# MainADC.net
KiCad netlist of a schematic drawn in Altium Designer
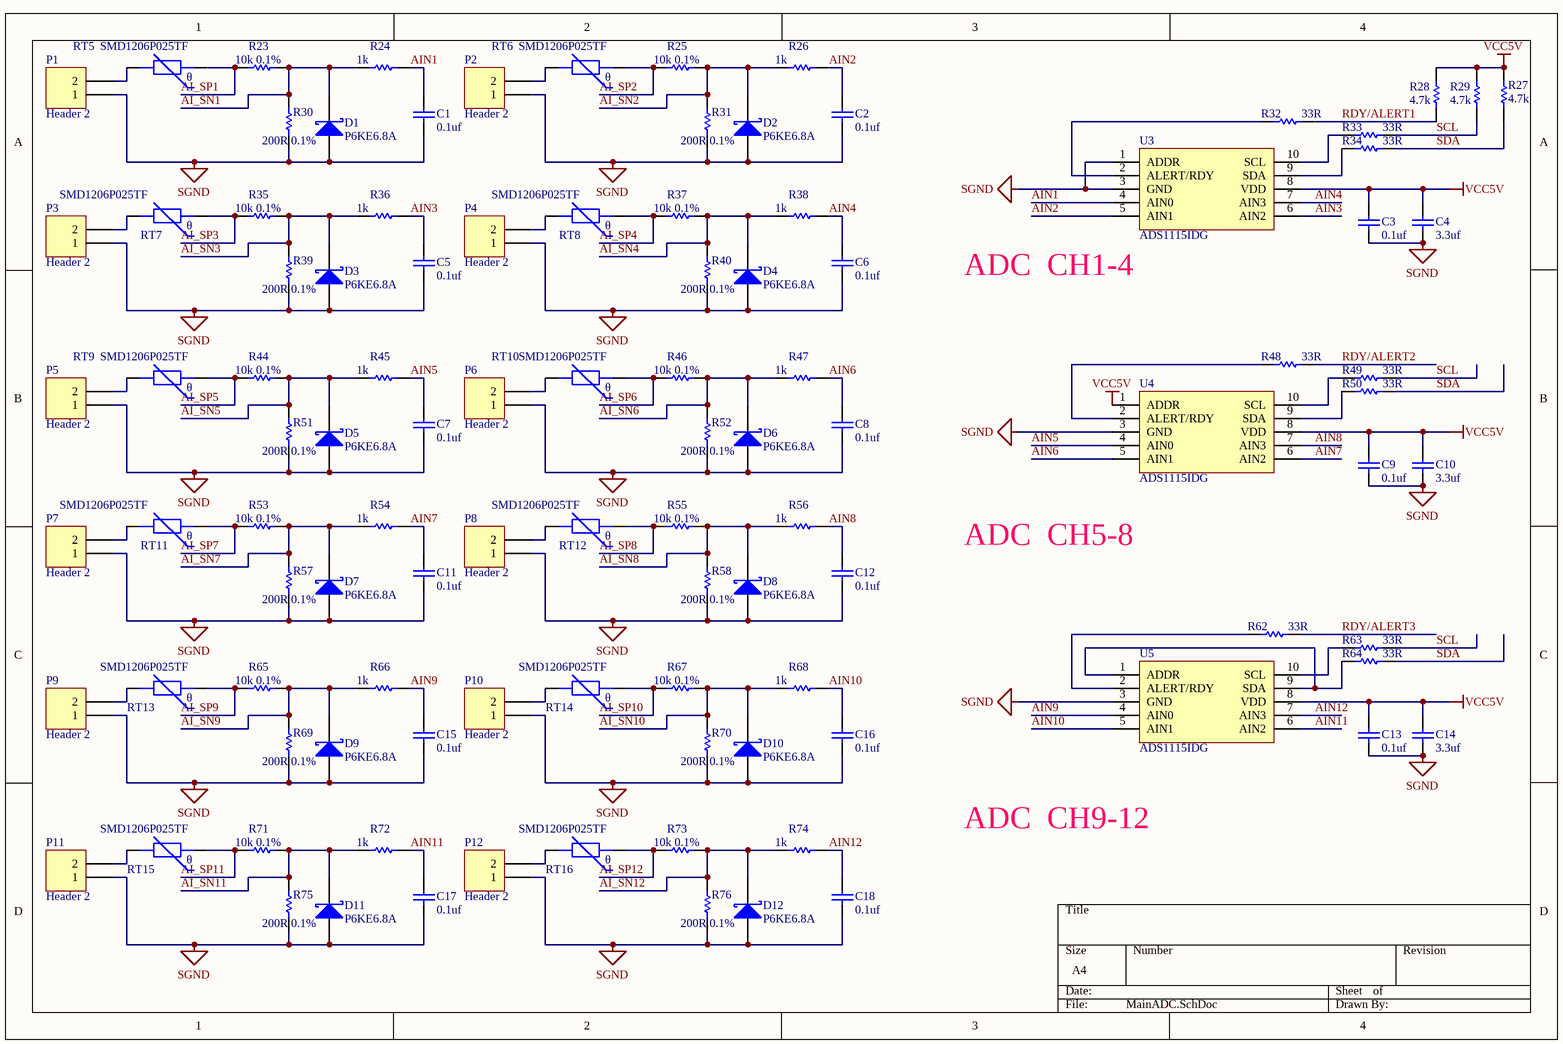
[diagram p0: MainADC.SchDoc]

(export (version "E")
  (design (tool "Eeschema 10.0.6"))
  (components
    (comp (ref "C1")
      (value "0.1uf")
      (footprint "C0805")
      (description "Capacitor")
      (fields
        (field (name "MANUFACTURER") "Generic Components")
        (field (name "Comment") "Cap")
        (field (name "PUBLISHER") "Altium Hobart Technology Centre")
      )
      (libsource (lib "Miscellaneous Devices") (part "Cap"))
    )
    (comp (ref "C2")
      (value "0.1uf")
      (footprint "C0805")
      (description "Capacitor")
      (fields
        (field (name "MANUFACTURER") "Generic Components")
        (field (name "Comment") "Cap")
        (field (name "PUBLISHER") "Altium Hobart Technology Centre")
      )
      (libsource (lib "Miscellaneous Devices") (part "Cap"))
    )
    (comp (ref "C3")
      (value "0.1uf")
      (footprint "C0805")
      (description "Capacitor")
      (fields
        (field (name "MANUFACTURER") "Generic Components")
        (field (name "Comment") "Cap")
        (field (name "PUBLISHER") "Altium Hobart Technology Centre")
      )
      (libsource (lib "Miscellaneous Devices") (part "Cap"))
    )
    (comp (ref "C4")
      (value "3.3uf")
      (footprint "C0805")
      (description "Capacitor")
      (fields
        (field (name "MANUFACTURER") "Generic Components")
        (field (name "Comment") "Cap")
        (field (name "PUBLISHER") "Altium Hobart Technology Centre")
      )
      (libsource (lib "Miscellaneous Devices") (part "Cap"))
    )
    (comp (ref "C5")
      (value "0.1uf")
      (footprint "C0805")
      (description "Capacitor")
      (fields
        (field (name "MANUFACTURER") "Generic Components")
        (field (name "Comment") "Cap")
        (field (name "PUBLISHER") "Altium Hobart Technology Centre")
      )
      (libsource (lib "Miscellaneous Devices") (part "Cap"))
    )
    (comp (ref "C6")
      (value "0.1uf")
      (footprint "C0805")
      (description "Capacitor")
      (fields
        (field (name "MANUFACTURER") "Generic Components")
        (field (name "Comment") "Cap")
        (field (name "PUBLISHER") "Altium Hobart Technology Centre")
      )
      (libsource (lib "Miscellaneous Devices") (part "Cap"))
    )
    (comp (ref "C7")
      (value "0.1uf")
      (footprint "C0805")
      (description "Capacitor")
      (fields
        (field (name "MANUFACTURER") "Generic Components")
        (field (name "Comment") "Cap")
        (field (name "PUBLISHER") "Altium Hobart Technology Centre")
      )
      (libsource (lib "Miscellaneous Devices") (part "Cap"))
    )
    (comp (ref "C8")
      (value "0.1uf")
      (footprint "C0805")
      (description "Capacitor")
      (fields
        (field (name "MANUFACTURER") "Generic Components")
        (field (name "Comment") "Cap")
        (field (name "PUBLISHER") "Altium Hobart Technology Centre")
      )
      (libsource (lib "Miscellaneous Devices") (part "Cap"))
    )
    (comp (ref "C9")
      (value "0.1uf")
      (footprint "C0805")
      (description "Capacitor")
      (fields
        (field (name "MANUFACTURER") "Generic Components")
        (field (name "Comment") "Cap")
        (field (name "PUBLISHER") "Altium Hobart Technology Centre")
      )
      (libsource (lib "Miscellaneous Devices") (part "Cap"))
    )
    (comp (ref "C10")
      (value "3.3uf")
      (footprint "C0805")
      (description "Capacitor")
      (fields
        (field (name "MANUFACTURER") "Generic Components")
        (field (name "Comment") "Cap")
        (field (name "PUBLISHER") "Altium Hobart Technology Centre")
      )
      (libsource (lib "Miscellaneous Devices") (part "Cap"))
    )
    (comp (ref "C11")
      (value "0.1uf")
      (footprint "C0805")
      (description "Capacitor")
      (fields
        (field (name "MANUFACTURER") "Generic Components")
        (field (name "Comment") "Cap")
        (field (name "PUBLISHER") "Altium Hobart Technology Centre")
      )
      (libsource (lib "Miscellaneous Devices") (part "Cap"))
    )
    (comp (ref "C12")
      (value "0.1uf")
      (footprint "C0805")
      (description "Capacitor")
      (fields
        (field (name "MANUFACTURER") "Generic Components")
        (field (name "Comment") "Cap")
        (field (name "PUBLISHER") "Altium Hobart Technology Centre")
      )
      (libsource (lib "Miscellaneous Devices") (part "Cap"))
    )
    (comp (ref "C13")
      (value "0.1uf")
      (footprint "C0805")
      (description "Capacitor")
      (fields
        (field (name "MANUFACTURER") "Generic Components")
        (field (name "Comment") "Cap")
        (field (name "PUBLISHER") "Altium Hobart Technology Centre")
      )
      (libsource (lib "Miscellaneous Devices") (part "Cap"))
    )
    (comp (ref "C14")
      (value "3.3uf")
      (footprint "C0805")
      (description "Capacitor")
      (fields
        (field (name "MANUFACTURER") "Generic Components")
        (field (name "Comment") "Cap")
        (field (name "PUBLISHER") "Altium Hobart Technology Centre")
      )
      (libsource (lib "Miscellaneous Devices") (part "Cap"))
    )
    (comp (ref "C15")
      (value "0.1uf")
      (footprint "C0805")
      (description "Capacitor")
      (fields
        (field (name "MANUFACTURER") "Generic Components")
        (field (name "Comment") "Cap")
        (field (name "PUBLISHER") "Altium Hobart Technology Centre")
      )
      (libsource (lib "Miscellaneous Devices") (part "Cap"))
    )
    (comp (ref "C16")
      (value "0.1uf")
      (footprint "C0805")
      (description "Capacitor")
      (fields
        (field (name "MANUFACTURER") "Generic Components")
        (field (name "Comment") "Cap")
        (field (name "PUBLISHER") "Altium Hobart Technology Centre")
      )
      (libsource (lib "Miscellaneous Devices") (part "Cap"))
    )
    (comp (ref "C17")
      (value "0.1uf")
      (footprint "C0805")
      (description "Capacitor")
      (fields
        (field (name "MANUFACTURER") "Generic Components")
        (field (name "Comment") "Cap")
        (field (name "PUBLISHER") "Altium Hobart Technology Centre")
      )
      (libsource (lib "Miscellaneous Devices") (part "Cap"))
    )
    (comp (ref "C18")
      (value "0.1uf")
      (footprint "C0805")
      (description "Capacitor")
      (fields
        (field (name "MANUFACTURER") "Generic Components")
        (field (name "Comment") "Cap")
        (field (name "PUBLISHER") "Altium Hobart Technology Centre")
      )
      (libsource (lib "Miscellaneous Devices") (part "Cap"))
    )
    (comp (ref "D1")
      (value "P6KE6.8A")
      (footprint "SMB")
      (description "Schottky Diode")
      (fields (field (name "PUBLISHER") "Altium Limited"))
      (libsource (lib "Miscellaneous Devices") (part "D Schottky"))
    )
    (comp (ref "D2")
      (value "P6KE6.8A")
      (footprint "SMB")
      (description "Schottky Diode")
      (fields (field (name "PUBLISHER") "Altium Limited"))
      (libsource (lib "Miscellaneous Devices") (part "D Schottky"))
    )
    (comp (ref "D3")
      (value "P6KE6.8A")
      (footprint "SMB")
      (description "Schottky Diode")
      (fields (field (name "PUBLISHER") "Altium Limited"))
      (libsource (lib "Miscellaneous Devices") (part "D Schottky"))
    )
    (comp (ref "D4")
      (value "P6KE6.8A")
      (footprint "SMB")
      (description "Schottky Diode")
      (fields (field (name "PUBLISHER") "Altium Limited"))
      (libsource (lib "Miscellaneous Devices") (part "D Schottky"))
    )
    (comp (ref "D5")
      (value "P6KE6.8A")
      (footprint "SMB")
      (description "Schottky Diode")
      (fields (field (name "PUBLISHER") "Altium Limited"))
      (libsource (lib "Miscellaneous Devices") (part "D Schottky"))
    )
    (comp (ref "D6")
      (value "P6KE6.8A")
      (footprint "SMB")
      (description "Schottky Diode")
      (fields (field (name "PUBLISHER") "Altium Limited"))
      (libsource (lib "Miscellaneous Devices") (part "D Schottky"))
    )
    (comp (ref "D7")
      (value "P6KE6.8A")
      (footprint "SMB")
      (description "Schottky Diode")
      (fields (field (name "PUBLISHER") "Altium Limited"))
      (libsource (lib "Miscellaneous Devices") (part "D Schottky"))
    )
    (comp (ref "D8")
      (value "P6KE6.8A")
      (footprint "SMB")
      (description "Schottky Diode")
      (fields (field (name "PUBLISHER") "Altium Limited"))
      (libsource (lib "Miscellaneous Devices") (part "D Schottky"))
    )
    (comp (ref "D9")
      (value "P6KE6.8A")
      (footprint "SMB")
      (description "Schottky Diode")
      (fields (field (name "PUBLISHER") "Altium Limited"))
      (libsource (lib "Miscellaneous Devices") (part "D Schottky"))
    )
    (comp (ref "D10")
      (value "P6KE6.8A")
      (footprint "SMB")
      (description "Schottky Diode")
      (fields (field (name "PUBLISHER") "Altium Limited"))
      (libsource (lib "Miscellaneous Devices") (part "D Schottky"))
    )
    (comp (ref "D11")
      (value "P6KE6.8A")
      (footprint "SMB")
      (description "Schottky Diode")
      (fields (field (name "PUBLISHER") "Altium Limited"))
      (libsource (lib "Miscellaneous Devices") (part "D Schottky"))
    )
    (comp (ref "D12")
      (value "P6KE6.8A")
      (footprint "SMB")
      (description "Schottky Diode")
      (fields (field (name "PUBLISHER") "Altium Limited"))
      (libsource (lib "Miscellaneous Devices") (part "D Schottky"))
    )
    (comp (ref "P1")
      (value "Header 2")
      (footprint "JIEKE_2PX508")
      (description "Header, 2-Pin")
      (fields (field (name "PUBLISHER") "Altium Limited"))
      (libsource (lib "Miscellaneous Connectors") (part "Header 2"))
    )
    (comp (ref "P2")
      (value "Header 2")
      (footprint "JIEKE_2PX508")
      (description "Header, 2-Pin")
      (fields (field (name "PUBLISHER") "Altium Limited"))
      (libsource (lib "Miscellaneous Connectors") (part "Header 2"))
    )
    (comp (ref "P3")
      (value "Header 2")
      (footprint "JIEKE_2PX508")
      (description "Header, 2-Pin")
      (fields (field (name "PUBLISHER") "Altium Limited"))
      (libsource (lib "Miscellaneous Connectors") (part "Header 2"))
    )
    (comp (ref "P4")
      (value "Header 2")
      (footprint "JIEKE_2PX508")
      (description "Header, 2-Pin")
      (fields (field (name "PUBLISHER") "Altium Limited"))
      (libsource (lib "Miscellaneous Connectors") (part "Header 2"))
    )
    (comp (ref "P5")
      (value "Header 2")
      (footprint "JIEKE_2PX508")
      (description "Header, 2-Pin")
      (fields (field (name "PUBLISHER") "Altium Limited"))
      (libsource (lib "Miscellaneous Connectors") (part "Header 2"))
    )
    (comp (ref "P6")
      (value "Header 2")
      (footprint "JIEKE_2PX508")
      (description "Header, 2-Pin")
      (fields (field (name "PUBLISHER") "Altium Limited"))
      (libsource (lib "Miscellaneous Connectors") (part "Header 2"))
    )
    (comp (ref "P7")
      (value "Header 2")
      (footprint "JIEKE_2PX508")
      (description "Header, 2-Pin")
      (fields (field (name "PUBLISHER") "Altium Limited"))
      (libsource (lib "Miscellaneous Connectors") (part "Header 2"))
    )
    (comp (ref "P8")
      (value "Header 2")
      (footprint "JIEKE_2PX508")
      (description "Header, 2-Pin")
      (fields (field (name "PUBLISHER") "Altium Limited"))
      (libsource (lib "Miscellaneous Connectors") (part "Header 2"))
    )
    (comp (ref "P9")
      (value "Header 2")
      (footprint "JIEKE_2PX508")
      (description "Header, 2-Pin")
      (fields (field (name "PUBLISHER") "Altium Limited"))
      (libsource (lib "Miscellaneous Connectors") (part "Header 2"))
    )
    (comp (ref "P10")
      (value "Header 2")
      (footprint "JIEKE_2PX508")
      (description "Header, 2-Pin")
      (fields (field (name "PUBLISHER") "Altium Limited"))
      (libsource (lib "Miscellaneous Connectors") (part "Header 2"))
    )
    (comp (ref "P11")
      (value "Header 2")
      (footprint "JIEKE_2PX508")
      (description "Header, 2-Pin")
      (fields (field (name "PUBLISHER") "Altium Limited"))
      (libsource (lib "Miscellaneous Connectors") (part "Header 2"))
    )
    (comp (ref "P12")
      (value "Header 2")
      (footprint "JIEKE_2PX508")
      (description "Header, 2-Pin")
      (fields (field (name "PUBLISHER") "Altium Limited"))
      (libsource (lib "Miscellaneous Connectors") (part "Header 2"))
    )
    (comp (ref "R23")
      (value "10k 0.1%")
      (footprint "0805")
      (description "Semiconductor Resistor")
      (fields (field (name "Comment") "Res Semi") (field (name "PUBLISHER") "Altium Limited"))
      (libsource (lib "Miscellaneous Devices") (part "Res Semi"))
    )
    (comp (ref "R24")
      (value "1k")
      (footprint "0805")
      (description "Semiconductor Resistor")
      (fields (field (name "Comment") "Res Semi") (field (name "PUBLISHER") "Altium Limited"))
      (libsource (lib "Miscellaneous Devices") (part "Res Semi"))
    )
    (comp (ref "R25")
      (value "10k 0.1%")
      (footprint "0805")
      (description "Semiconductor Resistor")
      (fields (field (name "Comment") "Res Semi") (field (name "PUBLISHER") "Altium Limited"))
      (libsource (lib "Miscellaneous Devices") (part "Res Semi"))
    )
    (comp (ref "R26")
      (value "1k")
      (footprint "0805")
      (description "Semiconductor Resistor")
      (fields (field (name "Comment") "Res Semi") (field (name "PUBLISHER") "Altium Limited"))
      (libsource (lib "Miscellaneous Devices") (part "Res Semi"))
    )
    (comp (ref "R27")
      (value "4.7k")
      (footprint "0805")
      (description "Semiconductor Resistor")
      (fields (field (name "Comment") "Res Semi") (field (name "PUBLISHER") "Altium Limited"))
      (libsource (lib "Miscellaneous Devices") (part "Res Semi"))
    )
    (comp (ref "R28")
      (value "4.7k")
      (footprint "0805")
      (description "Semiconductor Resistor")
      (fields (field (name "Comment") "Res Semi") (field (name "PUBLISHER") "Altium Limited"))
      (libsource (lib "Miscellaneous Devices") (part "Res Semi"))
    )
    (comp (ref "R29")
      (value "4.7k")
      (footprint "0805")
      (description "Semiconductor Resistor")
      (fields (field (name "Comment") "Res Semi") (field (name "PUBLISHER") "Altium Limited"))
      (libsource (lib "Miscellaneous Devices") (part "Res Semi"))
    )
    (comp (ref "R30")
      (value "200R 0.1%")
      (footprint "0805")
      (description "Semiconductor Resistor")
      (fields (field (name "Comment") "Res Semi") (field (name "PUBLISHER") "Altium Limited"))
      (libsource (lib "Miscellaneous Devices") (part "Res Semi"))
    )
    (comp (ref "R31")
      (value "200R 0.1%")
      (footprint "0805")
      (description "Semiconductor Resistor")
      (fields (field (name "Comment") "Res Semi") (field (name "PUBLISHER") "Altium Limited"))
      (libsource (lib "Miscellaneous Devices") (part "Res Semi"))
    )
    (comp (ref "R32")
      (value "33R")
      (footprint "0805")
      (description "Semiconductor Resistor")
      (fields (field (name "Comment") "Res Semi") (field (name "PUBLISHER") "Altium Limited"))
      (libsource (lib "Miscellaneous Devices") (part "Res Semi"))
    )
    (comp (ref "R33")
      (value "33R")
      (footprint "0805")
      (description "Semiconductor Resistor")
      (fields (field (name "Comment") "Res Semi") (field (name "PUBLISHER") "Altium Limited"))
      (libsource (lib "Miscellaneous Devices") (part "Res Semi"))
    )
    (comp (ref "R34")
      (value "33R")
      (footprint "0805")
      (description "Semiconductor Resistor")
      (fields (field (name "Comment") "Res Semi") (field (name "PUBLISHER") "Altium Limited"))
      (libsource (lib "Miscellaneous Devices") (part "Res Semi"))
    )
    (comp (ref "R35")
      (value "10k 0.1%")
      (footprint "0805")
      (description "Semiconductor Resistor")
      (fields (field (name "Comment") "Res Semi") (field (name "PUBLISHER") "Altium Limited"))
      (libsource (lib "Miscellaneous Devices") (part "Res Semi"))
    )
    (comp (ref "R36")
      (value "1k")
      (footprint "0805")
      (description "Semiconductor Resistor")
      (fields (field (name "Comment") "Res Semi") (field (name "PUBLISHER") "Altium Limited"))
      (libsource (lib "Miscellaneous Devices") (part "Res Semi"))
    )
    (comp (ref "R37")
      (value "10k 0.1%")
      (footprint "0805")
      (description "Semiconductor Resistor")
      (fields (field (name "Comment") "Res Semi") (field (name "PUBLISHER") "Altium Limited"))
      (libsource (lib "Miscellaneous Devices") (part "Res Semi"))
    )
    (comp (ref "R38")
      (value "1k")
      (footprint "0805")
      (description "Semiconductor Resistor")
      (fields (field (name "Comment") "Res Semi") (field (name "PUBLISHER") "Altium Limited"))
      (libsource (lib "Miscellaneous Devices") (part "Res Semi"))
    )
    (comp (ref "R39")
      (value "200R 0.1%")
      (footprint "0805")
      (description "Semiconductor Resistor")
      (fields (field (name "Comment") "Res Semi") (field (name "PUBLISHER") "Altium Limited"))
      (libsource (lib "Miscellaneous Devices") (part "Res Semi"))
    )
    (comp (ref "R40")
      (value "200R 0.1%")
      (footprint "0805")
      (description "Semiconductor Resistor")
      (fields (field (name "Comment") "Res Semi") (field (name "PUBLISHER") "Altium Limited"))
      (libsource (lib "Miscellaneous Devices") (part "Res Semi"))
    )
    (comp (ref "R44")
      (value "10k 0.1%")
      (footprint "0805")
      (description "Semiconductor Resistor")
      (fields (field (name "Comment") "Res Semi") (field (name "PUBLISHER") "Altium Limited"))
      (libsource (lib "Miscellaneous Devices") (part "Res Semi"))
    )
    (comp (ref "R45")
      (value "1k")
      (footprint "0805")
      (description "Semiconductor Resistor")
      (fields (field (name "Comment") "Res Semi") (field (name "PUBLISHER") "Altium Limited"))
      (libsource (lib "Miscellaneous Devices") (part "Res Semi"))
    )
    (comp (ref "R46")
      (value "10k 0.1%")
      (footprint "0805")
      (description "Semiconductor Resistor")
      (fields (field (name "Comment") "Res Semi") (field (name "PUBLISHER") "Altium Limited"))
      (libsource (lib "Miscellaneous Devices") (part "Res Semi"))
    )
    (comp (ref "R47")
      (value "1k")
      (footprint "0805")
      (description "Semiconductor Resistor")
      (fields (field (name "Comment") "Res Semi") (field (name "PUBLISHER") "Altium Limited"))
      (libsource (lib "Miscellaneous Devices") (part "Res Semi"))
    )
    (comp (ref "R48")
      (value "33R")
      (footprint "0805")
      (description "Semiconductor Resistor")
      (fields (field (name "Comment") "Res Semi") (field (name "PUBLISHER") "Altium Limited"))
      (libsource (lib "Miscellaneous Devices") (part "Res Semi"))
    )
    (comp (ref "R49")
      (value "33R")
      (footprint "0805")
      (description "Semiconductor Resistor")
      (fields (field (name "Comment") "Res Semi") (field (name "PUBLISHER") "Altium Limited"))
      (libsource (lib "Miscellaneous Devices") (part "Res Semi"))
    )
    (comp (ref "R50")
      (value "33R")
      (footprint "0805")
      (description "Semiconductor Resistor")
      (fields (field (name "Comment") "Res Semi") (field (name "PUBLISHER") "Altium Limited"))
      (libsource (lib "Miscellaneous Devices") (part "Res Semi"))
    )
    (comp (ref "R51")
      (value "200R 0.1%")
      (footprint "0805")
      (description "Semiconductor Resistor")
      (fields (field (name "Comment") "Res Semi") (field (name "PUBLISHER") "Altium Limited"))
      (libsource (lib "Miscellaneous Devices") (part "Res Semi"))
    )
    (comp (ref "R52")
      (value "200R 0.1%")
      (footprint "0805")
      (description "Semiconductor Resistor")
      (fields (field (name "Comment") "Res Semi") (field (name "PUBLISHER") "Altium Limited"))
      (libsource (lib "Miscellaneous Devices") (part "Res Semi"))
    )
    (comp (ref "R53")
      (value "10k 0.1%")
      (footprint "0805")
      (description "Semiconductor Resistor")
      (fields (field (name "Comment") "Res Semi") (field (name "PUBLISHER") "Altium Limited"))
      (libsource (lib "Miscellaneous Devices") (part "Res Semi"))
    )
    (comp (ref "R54")
      (value "1k")
      (footprint "0805")
      (description "Semiconductor Resistor")
      (fields (field (name "Comment") "Res Semi") (field (name "PUBLISHER") "Altium Limited"))
      (libsource (lib "Miscellaneous Devices") (part "Res Semi"))
    )
    (comp (ref "R55")
      (value "10k 0.1%")
      (footprint "0805")
      (description "Semiconductor Resistor")
      (fields (field (name "Comment") "Res Semi") (field (name "PUBLISHER") "Altium Limited"))
      (libsource (lib "Miscellaneous Devices") (part "Res Semi"))
    )
    (comp (ref "R56")
      (value "1k")
      (footprint "0805")
      (description "Semiconductor Resistor")
      (fields (field (name "Comment") "Res Semi") (field (name "PUBLISHER") "Altium Limited"))
      (libsource (lib "Miscellaneous Devices") (part "Res Semi"))
    )
    (comp (ref "R57")
      (value "200R 0.1%")
      (footprint "0805")
      (description "Semiconductor Resistor")
      (fields (field (name "Comment") "Res Semi") (field (name "PUBLISHER") "Altium Limited"))
      (libsource (lib "Miscellaneous Devices") (part "Res Semi"))
    )
    (comp (ref "R58")
      (value "200R 0.1%")
      (footprint "0805")
      (description "Semiconductor Resistor")
      (fields (field (name "Comment") "Res Semi") (field (name "PUBLISHER") "Altium Limited"))
      (libsource (lib "Miscellaneous Devices") (part "Res Semi"))
    )
    (comp (ref "R62")
      (value "33R")
      (footprint "0805")
      (description "Semiconductor Resistor")
      (fields (field (name "Comment") "Res Semi") (field (name "PUBLISHER") "Altium Limited"))
      (libsource (lib "Miscellaneous Devices") (part "Res Semi"))
    )
    (comp (ref "R63")
      (value "33R")
      (footprint "0805")
      (description "Semiconductor Resistor")
      (fields (field (name "Comment") "Res Semi") (field (name "PUBLISHER") "Altium Limited"))
      (libsource (lib "Miscellaneous Devices") (part "Res Semi"))
    )
    (comp (ref "R64")
      (value "33R")
      (footprint "0805")
      (description "Semiconductor Resistor")
      (fields (field (name "Comment") "Res Semi") (field (name "PUBLISHER") "Altium Limited"))
      (libsource (lib "Miscellaneous Devices") (part "Res Semi"))
    )
    (comp (ref "R65")
      (value "10k 0.1%")
      (footprint "0805")
      (description "Semiconductor Resistor")
      (fields (field (name "Comment") "Res Semi") (field (name "PUBLISHER") "Altium Limited"))
      (libsource (lib "Miscellaneous Devices") (part "Res Semi"))
    )
    (comp (ref "R66")
      (value "1k")
      (footprint "0805")
      (description "Semiconductor Resistor")
      (fields (field (name "Comment") "Res Semi") (field (name "PUBLISHER") "Altium Limited"))
      (libsource (lib "Miscellaneous Devices") (part "Res Semi"))
    )
    (comp (ref "R67")
      (value "10k 0.1%")
      (footprint "0805")
      (description "Semiconductor Resistor")
      (fields (field (name "Comment") "Res Semi") (field (name "PUBLISHER") "Altium Limited"))
      (libsource (lib "Miscellaneous Devices") (part "Res Semi"))
    )
    (comp (ref "R68")
      (value "1k")
      (footprint "0805")
      (description "Semiconductor Resistor")
      (fields (field (name "Comment") "Res Semi") (field (name "PUBLISHER") "Altium Limited"))
      (libsource (lib "Miscellaneous Devices") (part "Res Semi"))
    )
    (comp (ref "R69")
      (value "200R 0.1%")
      (footprint "0805")
      (description "Semiconductor Resistor")
      (fields (field (name "Comment") "Res Semi") (field (name "PUBLISHER") "Altium Limited"))
      (libsource (lib "Miscellaneous Devices") (part "Res Semi"))
    )
    (comp (ref "R70")
      (value "200R 0.1%")
      (footprint "0805")
      (description "Semiconductor Resistor")
      (fields (field (name "Comment") "Res Semi") (field (name "PUBLISHER") "Altium Limited"))
      (libsource (lib "Miscellaneous Devices") (part "Res Semi"))
    )
    (comp (ref "R71")
      (value "10k 0.1%")
      (footprint "0805")
      (description "Semiconductor Resistor")
      (fields (field (name "Comment") "Res Semi") (field (name "PUBLISHER") "Altium Limited"))
      (libsource (lib "Miscellaneous Devices") (part "Res Semi"))
    )
    (comp (ref "R72")
      (value "1k")
      (footprint "0805")
      (description "Semiconductor Resistor")
      (fields (field (name "Comment") "Res Semi") (field (name "PUBLISHER") "Altium Limited"))
      (libsource (lib "Miscellaneous Devices") (part "Res Semi"))
    )
    (comp (ref "R73")
      (value "10k 0.1%")
      (footprint "0805")
      (description "Semiconductor Resistor")
      (fields (field (name "Comment") "Res Semi") (field (name "PUBLISHER") "Altium Limited"))
      (libsource (lib "Miscellaneous Devices") (part "Res Semi"))
    )
    (comp (ref "R74")
      (value "1k")
      (footprint "0805")
      (description "Semiconductor Resistor")
      (fields (field (name "Comment") "Res Semi") (field (name "PUBLISHER") "Altium Limited"))
      (libsource (lib "Miscellaneous Devices") (part "Res Semi"))
    )
    (comp (ref "R75")
      (value "200R 0.1%")
      (footprint "0805")
      (description "Semiconductor Resistor")
      (fields (field (name "Comment") "Res Semi") (field (name "PUBLISHER") "Altium Limited"))
      (libsource (lib "Miscellaneous Devices") (part "Res Semi"))
    )
    (comp (ref "R76")
      (value "200R 0.1%")
      (footprint "0805")
      (description "Semiconductor Resistor")
      (fields (field (name "Comment") "Res Semi") (field (name "PUBLISHER") "Altium Limited"))
      (libsource (lib "Miscellaneous Devices") (part "Res Semi"))
    )
    (comp (ref "RT5")
      (value "SMD1206P025TF")
      (footprint "1206")
      (description "热敏电阻")
      (libsource (lib "*") (part "PTC"))
    )
    (comp (ref "RT6")
      (value "SMD1206P025TF")
      (footprint "1206")
      (description "热敏电阻")
      (libsource (lib "*") (part "PTC"))
    )
    (comp (ref "RT7")
      (value "SMD1206P025TF")
      (footprint "1206")
      (description "热敏电阻")
      (libsource (lib "*") (part "PTC"))
    )
    (comp (ref "RT8")
      (value "SMD1206P025TF")
      (footprint "1206")
      (description "热敏电阻")
      (libsource (lib "*") (part "PTC"))
    )
    (comp (ref "RT9")
      (value "SMD1206P025TF")
      (footprint "1206")
      (description "热敏电阻")
      (libsource (lib "*") (part "PTC"))
    )
    (comp (ref "RT10")
      (value "SMD1206P025TF")
      (footprint "1206")
      (description "热敏电阻")
      (libsource (lib "*") (part "PTC"))
    )
    (comp (ref "RT11")
      (value "SMD1206P025TF")
      (footprint "1206")
      (description "热敏电阻")
      (libsource (lib "*") (part "PTC"))
    )
    (comp (ref "RT12")
      (value "SMD1206P025TF")
      (footprint "1206")
      (description "热敏电阻")
      (libsource (lib "*") (part "PTC"))
    )
    (comp (ref "RT13")
      (value "SMD1206P025TF")
      (footprint "1206")
      (description "热敏电阻")
      (libsource (lib "*") (part "PTC"))
    )
    (comp (ref "RT14")
      (value "SMD1206P025TF")
      (footprint "1206")
      (description "热敏电阻")
      (libsource (lib "*") (part "PTC"))
    )
    (comp (ref "RT15")
      (value "SMD1206P025TF")
      (footprint "1206")
      (description "热敏电阻")
      (libsource (lib "*") (part "PTC"))
    )
    (comp (ref "RT16")
      (value "SMD1206P025TF")
      (footprint "1206")
      (description "热敏电阻")
      (libsource (lib "*") (part "PTC"))
    )
    (comp (ref "U3") (value "ADS1115IDG") (footprint "10uSOP_M") (libsource (lib "斜测仪") (part "ADS1115")))
    (comp (ref "U4") (value "ADS1115IDG") (footprint "10uSOP_M") (libsource (lib "斜测仪") (part "ADS1115")))
    (comp (ref "U5") (value "ADS1115IDG") (footprint "10uSOP_M") (libsource (lib "斜测仪") (part "ADS1115")))
  )
  (nets
    (net (code "1") (name "/AIN1") (class "Default")
      (node (ref "C1") (pin "1") (pinfunction "1_1") (pintype "passive"))
      (node (ref "R24") (pin "1") (pinfunction "1_1") (pintype "passive"))
      (node (ref "U3") (pin "4") (pinfunction "AIN0_4") (pintype "passive"))
    )
    (net (code "2") (name "/AIN2") (class "Default")
      (node (ref "C2") (pin "1") (pinfunction "1_1") (pintype "passive"))
      (node (ref "R26") (pin "1") (pinfunction "1_1") (pintype "passive"))
      (node (ref "U3") (pin "5") (pinfunction "AIN1_5") (pintype "passive"))
    )
    (net (code "3") (name "/AIN3") (class "Default")
      (node (ref "C5") (pin "1") (pinfunction "1_1") (pintype "passive"))
      (node (ref "R36") (pin "1") (pinfunction "1_1") (pintype "passive"))
      (node (ref "U3") (pin "6") (pinfunction "AIN2_6") (pintype "passive"))
    )
    (net (code "4") (name "/AIN4") (class "Default")
      (node (ref "C6") (pin "1") (pinfunction "1_1") (pintype "passive"))
      (node (ref "R38") (pin "1") (pinfunction "1_1") (pintype "passive"))
      (node (ref "U3") (pin "7") (pinfunction "AIN3_7") (pintype "passive"))
    )
    (net (code "5") (name "/AIN5") (class "Default")
      (node (ref "C7") (pin "1") (pinfunction "1_1") (pintype "passive"))
      (node (ref "R45") (pin "1") (pinfunction "1_1") (pintype "passive"))
      (node (ref "U4") (pin "4") (pinfunction "AIN0_4") (pintype "passive"))
    )
    (net (code "6") (name "/AIN6") (class "Default")
      (node (ref "C8") (pin "1") (pinfunction "1_1") (pintype "passive"))
      (node (ref "R47") (pin "1") (pinfunction "1_1") (pintype "passive"))
      (node (ref "U4") (pin "5") (pinfunction "AIN1_5") (pintype "passive"))
    )
    (net (code "7") (name "/AIN7") (class "Default")
      (node (ref "C11") (pin "1") (pinfunction "1_1") (pintype "passive"))
      (node (ref "R54") (pin "1") (pinfunction "1_1") (pintype "passive"))
      (node (ref "U4") (pin "6") (pinfunction "AIN2_6") (pintype "passive"))
    )
    (net (code "8") (name "/AIN8") (class "Default")
      (node (ref "C12") (pin "1") (pinfunction "1_1") (pintype "passive"))
      (node (ref "R56") (pin "1") (pinfunction "1_1") (pintype "passive"))
      (node (ref "U4") (pin "7") (pinfunction "AIN3_7") (pintype "passive"))
    )
    (net (code "9") (name "/AIN9") (class "Default")
      (node (ref "C15") (pin "1") (pinfunction "1_1") (pintype "passive"))
      (node (ref "R66") (pin "1") (pinfunction "1_1") (pintype "passive"))
      (node (ref "U5") (pin "4") (pinfunction "AIN0_4") (pintype "passive"))
    )
    (net (code "10") (name "/AIN10") (class "Default")
      (node (ref "C16") (pin "1") (pinfunction "1_1") (pintype "passive"))
      (node (ref "R68") (pin "1") (pinfunction "1_1") (pintype "passive"))
      (node (ref "U5") (pin "5") (pinfunction "AIN1_5") (pintype "passive"))
    )
    (net (code "11") (name "/AIN11") (class "Default")
      (node (ref "C17") (pin "1") (pinfunction "1_1") (pintype "passive"))
      (node (ref "R72") (pin "1") (pinfunction "1_1") (pintype "passive"))
      (node (ref "U5") (pin "6") (pinfunction "AIN2_6") (pintype "passive"))
    )
    (net (code "12") (name "/AIN12") (class "Default")
      (node (ref "C18") (pin "1") (pinfunction "1_1") (pintype "passive"))
      (node (ref "R74") (pin "1") (pinfunction "1_1") (pintype "passive"))
      (node (ref "U5") (pin "7") (pinfunction "AIN3_7") (pintype "passive"))
    )
    (net (code "13") (name "/AI_SN1") (class "Default")
      (node (ref "D1") (pin "2") (pinfunction "K_2") (pintype "passive"))
      (node (ref "R23") (pin "1") (pinfunction "1_1") (pintype "passive"))
      (node (ref "R24") (pin "2") (pinfunction "2_2") (pintype "passive"))
      (node (ref "R30") (pin "1") (pinfunction "1_1") (pintype "passive"))
    )
    (net (code "14") (name "/AI_SN2") (class "Default")
      (node (ref "D2") (pin "2") (pinfunction "K_2") (pintype "passive"))
      (node (ref "R25") (pin "1") (pinfunction "1_1") (pintype "passive"))
      (node (ref "R26") (pin "2") (pinfunction "2_2") (pintype "passive"))
      (node (ref "R31") (pin "1") (pinfunction "1_1") (pintype "passive"))
    )
    (net (code "15") (name "/AI_SN3") (class "Default")
      (node (ref "D3") (pin "2") (pinfunction "K_2") (pintype "passive"))
      (node (ref "R35") (pin "1") (pinfunction "1_1") (pintype "passive"))
      (node (ref "R36") (pin "2") (pinfunction "2_2") (pintype "passive"))
      (node (ref "R39") (pin "1") (pinfunction "1_1") (pintype "passive"))
    )
    (net (code "16") (name "/AI_SN4") (class "Default")
      (node (ref "D4") (pin "2") (pinfunction "K_2") (pintype "passive"))
      (node (ref "R37") (pin "1") (pinfunction "1_1") (pintype "passive"))
      (node (ref "R38") (pin "2") (pinfunction "2_2") (pintype "passive"))
      (node (ref "R40") (pin "1") (pinfunction "1_1") (pintype "passive"))
    )
    (net (code "17") (name "/AI_SN5") (class "Default")
      (node (ref "D5") (pin "2") (pinfunction "K_2") (pintype "passive"))
      (node (ref "R44") (pin "1") (pinfunction "1_1") (pintype "passive"))
      (node (ref "R45") (pin "2") (pinfunction "2_2") (pintype "passive"))
      (node (ref "R51") (pin "1") (pinfunction "1_1") (pintype "passive"))
    )
    (net (code "18") (name "/AI_SN6") (class "Default")
      (node (ref "D6") (pin "2") (pinfunction "K_2") (pintype "passive"))
      (node (ref "R46") (pin "1") (pinfunction "1_1") (pintype "passive"))
      (node (ref "R47") (pin "2") (pinfunction "2_2") (pintype "passive"))
      (node (ref "R52") (pin "1") (pinfunction "1_1") (pintype "passive"))
    )
    (net (code "19") (name "/AI_SN7") (class "Default")
      (node (ref "D7") (pin "2") (pinfunction "K_2") (pintype "passive"))
      (node (ref "R53") (pin "1") (pinfunction "1_1") (pintype "passive"))
      (node (ref "R54") (pin "2") (pinfunction "2_2") (pintype "passive"))
      (node (ref "R57") (pin "1") (pinfunction "1_1") (pintype "passive"))
    )
    (net (code "20") (name "/AI_SN8") (class "Default")
      (node (ref "D8") (pin "2") (pinfunction "K_2") (pintype "passive"))
      (node (ref "R55") (pin "1") (pinfunction "1_1") (pintype "passive"))
      (node (ref "R56") (pin "2") (pinfunction "2_2") (pintype "passive"))
      (node (ref "R58") (pin "1") (pinfunction "1_1") (pintype "passive"))
    )
    (net (code "21") (name "/AI_SN9") (class "Default")
      (node (ref "D9") (pin "2") (pinfunction "K_2") (pintype "passive"))
      (node (ref "R65") (pin "1") (pinfunction "1_1") (pintype "passive"))
      (node (ref "R66") (pin "2") (pinfunction "2_2") (pintype "passive"))
      (node (ref "R69") (pin "1") (pinfunction "1_1") (pintype "passive"))
    )
    (net (code "22") (name "/AI_SN10") (class "Default")
      (node (ref "D10") (pin "2") (pinfunction "K_2") (pintype "passive"))
      (node (ref "R67") (pin "1") (pinfunction "1_1") (pintype "passive"))
      (node (ref "R68") (pin "2") (pinfunction "2_2") (pintype "passive"))
      (node (ref "R70") (pin "1") (pinfunction "1_1") (pintype "passive"))
    )
    (net (code "23") (name "/AI_SN11") (class "Default")
      (node (ref "D11") (pin "2") (pinfunction "K_2") (pintype "passive"))
      (node (ref "R71") (pin "1") (pinfunction "1_1") (pintype "passive"))
      (node (ref "R72") (pin "2") (pinfunction "2_2") (pintype "passive"))
      (node (ref "R75") (pin "1") (pinfunction "1_1") (pintype "passive"))
    )
    (net (code "24") (name "/AI_SN12") (class "Default")
      (node (ref "D12") (pin "2") (pinfunction "K_2") (pintype "passive"))
      (node (ref "R73") (pin "1") (pinfunction "1_1") (pintype "passive"))
      (node (ref "R74") (pin "2") (pinfunction "2_2") (pintype "passive"))
      (node (ref "R76") (pin "1") (pinfunction "1_1") (pintype "passive"))
    )
    (net (code "25") (name "/AI_SP1") (class "Default")
      (node (ref "R23") (pin "2") (pinfunction "2_2") (pintype "passive"))
      (node (ref "RT5") (pin "2") (pintype "passive"))
    )
    (net (code "26") (name "/AI_SP2") (class "Default")
      (node (ref "R25") (pin "2") (pinfunction "2_2") (pintype "passive"))
      (node (ref "RT6") (pin "2") (pintype "passive"))
    )
    (net (code "27") (name "/AI_SP3") (class "Default")
      (node (ref "R35") (pin "2") (pinfunction "2_2") (pintype "passive"))
      (node (ref "RT7") (pin "2") (pintype "passive"))
    )
    (net (code "28") (name "/AI_SP4") (class "Default")
      (node (ref "R37") (pin "2") (pinfunction "2_2") (pintype "passive"))
      (node (ref "RT8") (pin "2") (pintype "passive"))
    )
    (net (code "29") (name "/AI_SP5") (class "Default")
      (node (ref "R44") (pin "2") (pinfunction "2_2") (pintype "passive"))
      (node (ref "RT9") (pin "2") (pintype "passive"))
    )
    (net (code "30") (name "/AI_SP6") (class "Default")
      (node (ref "R46") (pin "2") (pinfunction "2_2") (pintype "passive"))
      (node (ref "RT10") (pin "2") (pintype "passive"))
    )
    (net (code "31") (name "/AI_SP7") (class "Default")
      (node (ref "R53") (pin "2") (pinfunction "2_2") (pintype "passive"))
      (node (ref "RT11") (pin "2") (pintype "passive"))
    )
    (net (code "32") (name "/AI_SP8") (class "Default")
      (node (ref "R55") (pin "2") (pinfunction "2_2") (pintype "passive"))
      (node (ref "RT12") (pin "2") (pintype "passive"))
    )
    (net (code "33") (name "/AI_SP9") (class "Default")
      (node (ref "R65") (pin "2") (pinfunction "2_2") (pintype "passive"))
      (node (ref "RT13") (pin "2") (pintype "passive"))
    )
    (net (code "34") (name "/AI_SP10") (class "Default")
      (node (ref "R67") (pin "2") (pinfunction "2_2") (pintype "passive"))
      (node (ref "RT14") (pin "2") (pintype "passive"))
    )
    (net (code "35") (name "/AI_SP11") (class "Default")
      (node (ref "R71") (pin "2") (pinfunction "2_2") (pintype "passive"))
      (node (ref "RT15") (pin "2") (pintype "passive"))
    )
    (net (code "36") (name "/AI_SP12") (class "Default")
      (node (ref "R73") (pin "2") (pinfunction "2_2") (pintype "passive"))
      (node (ref "RT16") (pin "2") (pintype "passive"))
    )
    (net (code "37") (name "/RDY{slash}ALERT1") (class "Default")
      (node (ref "R28") (pin "2") (pinfunction "2_2") (pintype "passive"))
      (node (ref "R32") (pin "1") (pinfunction "1_1") (pintype "passive"))
    )
    (net (code "38") (name "/RDY{slash}ALERT2") (class "Default")
      (node (ref "R48") (pin "1") (pinfunction "1_1") (pintype "passive"))
    )
    (net (code "39") (name "/RDY{slash}ALERT3") (class "Default")
      (node (ref "R62") (pin "1") (pinfunction "1_1") (pintype "passive"))
    )
    (net (code "40") (name "/SCL") (class "Default")
      (node (ref "R29") (pin "2") (pinfunction "2_2") (pintype "passive"))
      (node (ref "R33") (pin "1") (pinfunction "1_1") (pintype "passive"))
      (node (ref "R49") (pin "1") (pinfunction "1_1") (pintype "passive"))
      (node (ref "R63") (pin "1") (pinfunction "1_1") (pintype "passive"))
    )
    (net (code "41") (name "/SDA") (class "Default")
      (node (ref "R27") (pin "2") (pinfunction "2_2") (pintype "passive"))
      (node (ref "R34") (pin "1") (pinfunction "1_1") (pintype "passive"))
      (node (ref "R50") (pin "1") (pinfunction "1_1") (pintype "passive"))
      (node (ref "R64") (pin "1") (pinfunction "1_1") (pintype "passive"))
    )
    (net (code "42") (name "Net-(P1-Pad2)") (class "Default")
      (node (ref "P1") (pin "2") (pinfunction "2_2") (pintype "passive"))
      (node (ref "RT5") (pin "1") (pintype "passive"))
    )
    (net (code "43") (name "Net-(P2-Pad2)") (class "Default")
      (node (ref "P2") (pin "2") (pinfunction "2_2") (pintype "passive"))
      (node (ref "RT6") (pin "1") (pintype "passive"))
    )
    (net (code "44") (name "Net-(P3-Pad2)") (class "Default")
      (node (ref "P3") (pin "2") (pinfunction "2_2") (pintype "passive"))
      (node (ref "RT7") (pin "1") (pintype "passive"))
    )
    (net (code "45") (name "Net-(P4-Pad2)") (class "Default")
      (node (ref "P4") (pin "2") (pinfunction "2_2") (pintype "passive"))
      (node (ref "RT8") (pin "1") (pintype "passive"))
    )
    (net (code "46") (name "Net-(P5-Pad2)") (class "Default")
      (node (ref "P5") (pin "2") (pinfunction "2_2") (pintype "passive"))
      (node (ref "RT9") (pin "1") (pintype "passive"))
    )
    (net (code "47") (name "Net-(P6-Pad2)") (class "Default")
      (node (ref "P6") (pin "2") (pinfunction "2_2") (pintype "passive"))
      (node (ref "RT10") (pin "1") (pintype "passive"))
    )
    (net (code "48") (name "Net-(P7-Pad2)") (class "Default")
      (node (ref "P7") (pin "2") (pinfunction "2_2") (pintype "passive"))
      (node (ref "RT11") (pin "1") (pintype "passive"))
    )
    (net (code "49") (name "Net-(P8-Pad2)") (class "Default")
      (node (ref "P8") (pin "2") (pinfunction "2_2") (pintype "passive"))
      (node (ref "RT12") (pin "1") (pintype "passive"))
    )
    (net (code "50") (name "Net-(P9-Pad2)") (class "Default")
      (node (ref "P9") (pin "2") (pinfunction "2_2") (pintype "passive"))
      (node (ref "RT13") (pin "1") (pintype "passive"))
    )
    (net (code "51") (name "Net-(P10-Pad2)") (class "Default")
      (node (ref "P10") (pin "2") (pinfunction "2_2") (pintype "passive"))
      (node (ref "RT14") (pin "1") (pintype "passive"))
    )
    (net (code "52") (name "Net-(P11-Pad2)") (class "Default")
      (node (ref "P11") (pin "2") (pinfunction "2_2") (pintype "passive"))
      (node (ref "RT15") (pin "1") (pintype "passive"))
    )
    (net (code "53") (name "Net-(P12-Pad2)") (class "Default")
      (node (ref "P12") (pin "2") (pinfunction "2_2") (pintype "passive"))
      (node (ref "RT16") (pin "1") (pintype "passive"))
    )
    (net (code "54") (name "Net-(U3-ALERT{slash}RDY)") (class "Default")
      (node (ref "R32") (pin "2") (pinfunction "2_2") (pintype "passive"))
      (node (ref "U3") (pin "2") (pinfunction "ALERT/RDY_2") (pintype "passive"))
    )
    (net (code "55") (name "Net-(U3-SCL)") (class "Default")
      (node (ref "R33") (pin "2") (pinfunction "2_2") (pintype "passive"))
      (node (ref "U3") (pin "10") (pinfunction "SCL_10") (pintype "passive"))
    )
    (net (code "56") (name "Net-(U3-SDA)") (class "Default")
      (node (ref "R34") (pin "2") (pinfunction "2_2") (pintype "passive"))
      (node (ref "U3") (pin "9") (pinfunction "SDA_9") (pintype "passive"))
    )
    (net (code "57") (name "Net-(U4-ALERT{slash}RDY)") (class "Default")
      (node (ref "R48") (pin "2") (pinfunction "2_2") (pintype "passive"))
      (node (ref "U4") (pin "2") (pinfunction "ALERT/RDY_2") (pintype "passive"))
    )
    (net (code "58") (name "Net-(U4-SCL)") (class "Default")
      (node (ref "R49") (pin "2") (pinfunction "2_2") (pintype "passive"))
      (node (ref "U4") (pin "10") (pinfunction "SCL_10") (pintype "passive"))
    )
    (net (code "59") (name "Net-(U4-SDA)") (class "Default")
      (node (ref "R50") (pin "2") (pinfunction "2_2") (pintype "passive"))
      (node (ref "U4") (pin "9") (pinfunction "SDA_9") (pintype "passive"))
    )
    (net (code "60") (name "Net-(U5-ADDR)") (class "Default")
      (node (ref "R64") (pin "2") (pinfunction "2_2") (pintype "passive"))
      (node (ref "U5") (pin "1") (pinfunction "ADDR_1") (pintype "passive"))
      (node (ref "U5") (pin "9") (pinfunction "SDA_9") (pintype "passive"))
    )
    (net (code "61") (name "Net-(U5-ALERT{slash}RDY)") (class "Default")
      (node (ref "R62") (pin "2") (pinfunction "2_2") (pintype "passive"))
      (node (ref "U5") (pin "2") (pinfunction "ALERT/RDY_2") (pintype "passive"))
    )
    (net (code "62") (name "Net-(U5-SCL)") (class "Default")
      (node (ref "R63") (pin "2") (pinfunction "2_2") (pintype "passive"))
      (node (ref "U5") (pin "10") (pinfunction "SCL_10") (pintype "passive"))
    )
    (net (code "63") (name "SGND") (class "Default")
      (node (ref "C1") (pin "2") (pinfunction "2_2") (pintype "passive"))
      (node (ref "C10") (pin "2") (pinfunction "2_2") (pintype "passive"))
      (node (ref "C11") (pin "2") (pinfunction "2_2") (pintype "passive"))
      (node (ref "C12") (pin "2") (pinfunction "2_2") (pintype "passive"))
      (node (ref "C13") (pin "2") (pinfunction "2_2") (pintype "passive"))
      (node (ref "C14") (pin "2") (pinfunction "2_2") (pintype "passive"))
      (node (ref "C15") (pin "2") (pinfunction "2_2") (pintype "passive"))
      (node (ref "C16") (pin "2") (pinfunction "2_2") (pintype "passive"))
      (node (ref "C17") (pin "2") (pinfunction "2_2") (pintype "passive"))
      (node (ref "C18") (pin "2") (pinfunction "2_2") (pintype "passive"))
      (node (ref "C2") (pin "2") (pinfunction "2_2") (pintype "passive"))
      (node (ref "C3") (pin "2") (pinfunction "2_2") (pintype "passive"))
      (node (ref "C4") (pin "2") (pinfunction "2_2") (pintype "passive"))
      (node (ref "C5") (pin "2") (pinfunction "2_2") (pintype "passive"))
      (node (ref "C6") (pin "2") (pinfunction "2_2") (pintype "passive"))
      (node (ref "C7") (pin "2") (pinfunction "2_2") (pintype "passive"))
      (node (ref "C8") (pin "2") (pinfunction "2_2") (pintype "passive"))
      (node (ref "C9") (pin "2") (pinfunction "2_2") (pintype "passive"))
      (node (ref "D1") (pin "1") (pinfunction "A_1") (pintype "passive"))
      (node (ref "D10") (pin "1") (pinfunction "A_1") (pintype "passive"))
      (node (ref "D11") (pin "1") (pinfunction "A_1") (pintype "passive"))
      (node (ref "D12") (pin "1") (pinfunction "A_1") (pintype "passive"))
      (node (ref "D2") (pin "1") (pinfunction "A_1") (pintype "passive"))
      (node (ref "D3") (pin "1") (pinfunction "A_1") (pintype "passive"))
      (node (ref "D4") (pin "1") (pinfunction "A_1") (pintype "passive"))
      (node (ref "D5") (pin "1") (pinfunction "A_1") (pintype "passive"))
      (node (ref "D6") (pin "1") (pinfunction "A_1") (pintype "passive"))
      (node (ref "D7") (pin "1") (pinfunction "A_1") (pintype "passive"))
      (node (ref "D8") (pin "1") (pinfunction "A_1") (pintype "passive"))
      (node (ref "D9") (pin "1") (pinfunction "A_1") (pintype "passive"))
      (node (ref "P1") (pin "1") (pinfunction "1_1") (pintype "passive"))
      (node (ref "P10") (pin "1") (pinfunction "1_1") (pintype "passive"))
      (node (ref "P11") (pin "1") (pinfunction "1_1") (pintype "passive"))
      (node (ref "P12") (pin "1") (pinfunction "1_1") (pintype "passive"))
      (node (ref "P2") (pin "1") (pinfunction "1_1") (pintype "passive"))
      (node (ref "P3") (pin "1") (pinfunction "1_1") (pintype "passive"))
      (node (ref "P4") (pin "1") (pinfunction "1_1") (pintype "passive"))
      (node (ref "P5") (pin "1") (pinfunction "1_1") (pintype "passive"))
      (node (ref "P6") (pin "1") (pinfunction "1_1") (pintype "passive"))
      (node (ref "P7") (pin "1") (pinfunction "1_1") (pintype "passive"))
      (node (ref "P8") (pin "1") (pinfunction "1_1") (pintype "passive"))
      (node (ref "P9") (pin "1") (pinfunction "1_1") (pintype "passive"))
      (node (ref "R30") (pin "2") (pinfunction "2_2") (pintype "passive"))
      (node (ref "R31") (pin "2") (pinfunction "2_2") (pintype "passive"))
      (node (ref "R39") (pin "2") (pinfunction "2_2") (pintype "passive"))
      (node (ref "R40") (pin "2") (pinfunction "2_2") (pintype "passive"))
      (node (ref "R51") (pin "2") (pinfunction "2_2") (pintype "passive"))
      (node (ref "R52") (pin "2") (pinfunction "2_2") (pintype "passive"))
      (node (ref "R57") (pin "2") (pinfunction "2_2") (pintype "passive"))
      (node (ref "R58") (pin "2") (pinfunction "2_2") (pintype "passive"))
      (node (ref "R69") (pin "2") (pinfunction "2_2") (pintype "passive"))
      (node (ref "R70") (pin "2") (pinfunction "2_2") (pintype "passive"))
      (node (ref "R75") (pin "2") (pinfunction "2_2") (pintype "passive"))
      (node (ref "R76") (pin "2") (pinfunction "2_2") (pintype "passive"))
      (node (ref "U3") (pin "1") (pinfunction "ADDR_1") (pintype "passive"))
      (node (ref "U3") (pin "3") (pinfunction "GND_3") (pintype "passive"))
      (node (ref "U4") (pin "3") (pinfunction "GND_3") (pintype "passive"))
      (node (ref "U5") (pin "3") (pinfunction "GND_3") (pintype "passive"))
    )
    (net (code "64") (name "VCC5V") (class "Default")
      (node (ref "C10") (pin "1") (pinfunction "1_1") (pintype "passive"))
      (node (ref "C13") (pin "1") (pinfunction "1_1") (pintype "passive"))
      (node (ref "C14") (pin "1") (pinfunction "1_1") (pintype "passive"))
      (node (ref "C3") (pin "1") (pinfunction "1_1") (pintype "passive"))
      (node (ref "C4") (pin "1") (pinfunction "1_1") (pintype "passive"))
      (node (ref "C9") (pin "1") (pinfunction "1_1") (pintype "passive"))
      (node (ref "R27") (pin "1") (pinfunction "1_1") (pintype "passive"))
      (node (ref "R28") (pin "1") (pinfunction "1_1") (pintype "passive"))
      (node (ref "R29") (pin "1") (pinfunction "1_1") (pintype "passive"))
      (node (ref "U3") (pin "8") (pinfunction "VDD_8") (pintype "passive"))
      (node (ref "U4") (pin "1") (pinfunction "ADDR_1") (pintype "passive"))
      (node (ref "U4") (pin "8") (pinfunction "VDD_8") (pintype "passive"))
      (node (ref "U5") (pin "8") (pinfunction "VDD_8") (pintype "passive"))
    )
  )
)
